# OPAMP.net
KiCad netlist of a schematic drawn in Altium Designer
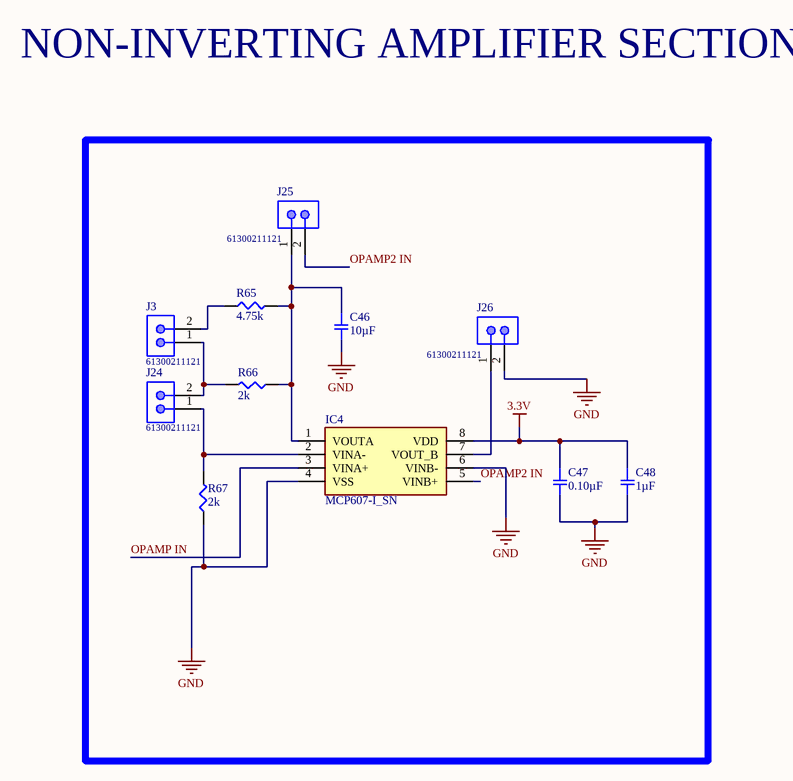
[diagram p0: OPAMP.SchDoc]

(export (version "E")
  (design (tool "Eeschema 10.0.6"))
  (components
    (comp (ref "C46")
      (value "10µF")
      (footprint "SMD-0805C")
      (description "CAP CER 10UF 10V X7R 0805")
      (fields
        (field (name "DIGI-KEY PART NUMBER") "490-12646-1-ND")
        (field (name "PART NUMBER") "GCJ21BR71A106KE01L")
      )
      (libsource (lib "capacitor_murata_0805") (part "GCJ21BR71A106KE01L"))
    )
    (comp (ref "C47")
      (value "0.10µF")
      (footprint "SMD-0805C")
      (description "CAP CER 0.1UF 50V X7R 0805")
      (fields
        (field (name "DIGI-KEY PART NUMBER") "490-11955-1-ND")
        (field (name "PART NUMBER") "GCD21BR71H104KA01L")
      )
      (libsource (lib "capacitor_murata_0805") (part "GCD21BR71H104KA01L"))
    )
    (comp (ref "C48")
      (value "1µF")
      (footprint "SMD-0805C")
      (description "CAP CER 1UF 16V X7R 0805")
      (fields
        (field (name "DIGI-KEY PART NUMBER") "490-5800-1-ND")
        (field (name "PART NUMBER") "GCJ219R71C105KA01D")
      )
      (libsource (lib "capacitor_murata_0805") (part "GCJ219R71C105KA01D"))
    )
    (comp (ref "IC4")
      (value "MCP607-I_SN")
      (footprint "SamacSys:SOIC127P600X175-8N")
      (description "Integrated Circuit")
      (fields
        (field (name "MANUFACTURER_PART_NUMBER") "MCP607-I/SN")
        (field (name "MOUSER PART NUMBER") "579-MCP607-I/SN")
      )
      (libsource (lib "*") (part "MCP607-I_SN"))
    )
    (comp (ref "J3")
      (value "61300211121")
      (footprint "61300211121")
      (description "WR-PHD Pin Header, THT, pitch 2.54mm, Single Row, Vertical, 2pin")
      (fields (field (name "PUBLISHER") "Wurth Elektronik"))
      (libsource (lib "SIL_Connectors WR-PHD_rev19a") (part "61300211121"))
    )
    (comp (ref "J24")
      (value "61300211121")
      (footprint "61300211121")
      (description "WR-PHD Pin Header, THT, pitch 2.54mm, Single Row, Vertical, 2pin")
      (fields (field (name "PUBLISHER") "Wurth Elektronik"))
      (libsource (lib "SIL_Connectors WR-PHD_rev19a") (part "61300211121"))
    )
    (comp (ref "J25")
      (value "61300211121")
      (footprint "61300211121")
      (description "WR-PHD Pin Header, THT, pitch 2.54mm, Single Row, Vertical, 2pin")
      (fields (field (name "PUBLISHER") "Wurth Elektronik"))
      (libsource (lib "SIL_Connectors WR-PHD_rev19a") (part "61300211121"))
    )
    (comp (ref "J26")
      (value "61300211121")
      (footprint "61300211121")
      (description "WR-PHD Pin Header, THT, pitch 2.54mm, Single Row, Vertical, 2pin")
      (fields (field (name "PUBLISHER") "Wurth Elektronik"))
      (libsource (lib "SIL_Connectors WR-PHD_rev19a") (part "61300211121"))
    )
    (comp (ref "R65")
      (value "4.75k")
      (footprint "SMD-0805-RES")
      (description "RES SMD 4.75K OHM 1% 1/8W 0805")
      (fields
        (field (name "PART NUMBER") "ERJ-6ENF4751V")
        (field (name "DIGI-KEY PART NUMBER") "P4.75KCCT-ND")
      )
      (libsource (lib "Panasonic_ERJ_0805") (part "ERJ-6ENF4751V"))
    )
    (comp (ref "R66")
      (value "2k")
      (footprint "SMD-0805-RES")
      (description "RES SMD 2K OHM 0.5% 1/2W 0805")
      (fields
        (field (name "PART NUMBER") "ERJ-P06D2001V")
        (field (name "DIGI-KEY PART NUMBER") "P16044CT-ND")
      )
      (libsource (lib "Panasonic_ERJ_0805") (part "ERJ-P06D2001V"))
    )
    (comp (ref "R67")
      (value "2k")
      (footprint "SMD-0805-RES")
      (description "RES SMD 2K OHM 0.5% 1/2W 0805")
      (fields
        (field (name "PART NUMBER") "ERJ-P06D2001V")
        (field (name "DIGI-KEY PART NUMBER") "P16044CT-ND")
      )
      (libsource (lib "Panasonic_ERJ_0805") (part "ERJ-P06D2001V"))
    )
  )
  (nets
    (net (code "1") (name "/OPAMP IN") (class "Default")
      (node (ref "IC4") (pin "3") (pinfunction "VINA+_3") (pintype "passive"))
    )
    (net (code "2") (name "/OPAMP2 IN") (class "Default")
      (node (ref "IC4") (pin "5") (pinfunction "VINB+_5") (pintype "passive"))
      (node (ref "J25") (pin "2") (pinfunction "2_2") (pintype "passive"))
    )
    (net (code "3") (name "3.3V") (class "Default")
      (node (ref "C47") (pin "1") (pinfunction "1_1") (pintype "passive"))
      (node (ref "C48") (pin "1") (pinfunction "1_1") (pintype "passive"))
      (node (ref "IC4") (pin "8") (pinfunction "VDD_8") (pintype "passive"))
    )
    (net (code "4") (name "GND") (class "Default")
      (node (ref "C46") (pin "2") (pinfunction "2_2") (pintype "passive"))
      (node (ref "C47") (pin "2") (pinfunction "2_2") (pintype "passive"))
      (node (ref "C48") (pin "2") (pinfunction "2_2") (pintype "passive"))
      (node (ref "IC4") (pin "4") (pinfunction "VSS_4") (pintype "passive"))
      (node (ref "IC4") (pin "6") (pinfunction "VINB-_6") (pintype "passive"))
      (node (ref "J26") (pin "2") (pinfunction "2_2") (pintype "passive"))
      (node (ref "R67") (pin "1") (pinfunction "1_1") (pintype "passive"))
    )
    (net (code "5") (name "Net-(IC4-VINA-)") (class "Default")
      (node (ref "IC4") (pin "2") (pinfunction "VINA-_2") (pintype "passive"))
      (node (ref "J24") (pin "1") (pinfunction "1_1") (pintype "passive"))
      (node (ref "R67") (pin "2") (pinfunction "2_2") (pintype "passive"))
    )
    (net (code "6") (name "Net-(IC4-VOUTA)") (class "Default")
      (node (ref "C46") (pin "1") (pinfunction "1_1") (pintype "passive"))
      (node (ref "IC4") (pin "1") (pinfunction "VOUTA_1") (pintype "passive"))
      (node (ref "J25") (pin "1") (pinfunction "1_1") (pintype "passive"))
      (node (ref "R65") (pin "2") (pinfunction "2_2") (pintype "passive"))
      (node (ref "R66") (pin "1") (pinfunction "1_1") (pintype "passive"))
    )
    (net (code "7") (name "Net-(IC4-VOUT_B)") (class "Default")
      (node (ref "IC4") (pin "7") (pinfunction "VOUT_B_7") (pintype "passive"))
      (node (ref "J26") (pin "1") (pinfunction "1_1") (pintype "passive"))
    )
    (net (code "8") (name "Net-(J3-Pad2)") (class "Default")
      (node (ref "J3") (pin "2") (pinfunction "2_2") (pintype "passive"))
      (node (ref "R65") (pin "1") (pinfunction "1_1") (pintype "passive"))
    )
    (net (code "9") (name "Net-(J24-Pad2)") (class "Default")
      (node (ref "J24") (pin "2") (pinfunction "2_2") (pintype "passive"))
      (node (ref "J3") (pin "1") (pinfunction "1_1") (pintype "passive"))
      (node (ref "R66") (pin "2") (pinfunction "2_2") (pintype "passive"))
    )
  )
)
